# F4FlightController.net
KiCad netlist of a schematic drawn in Altium Designer
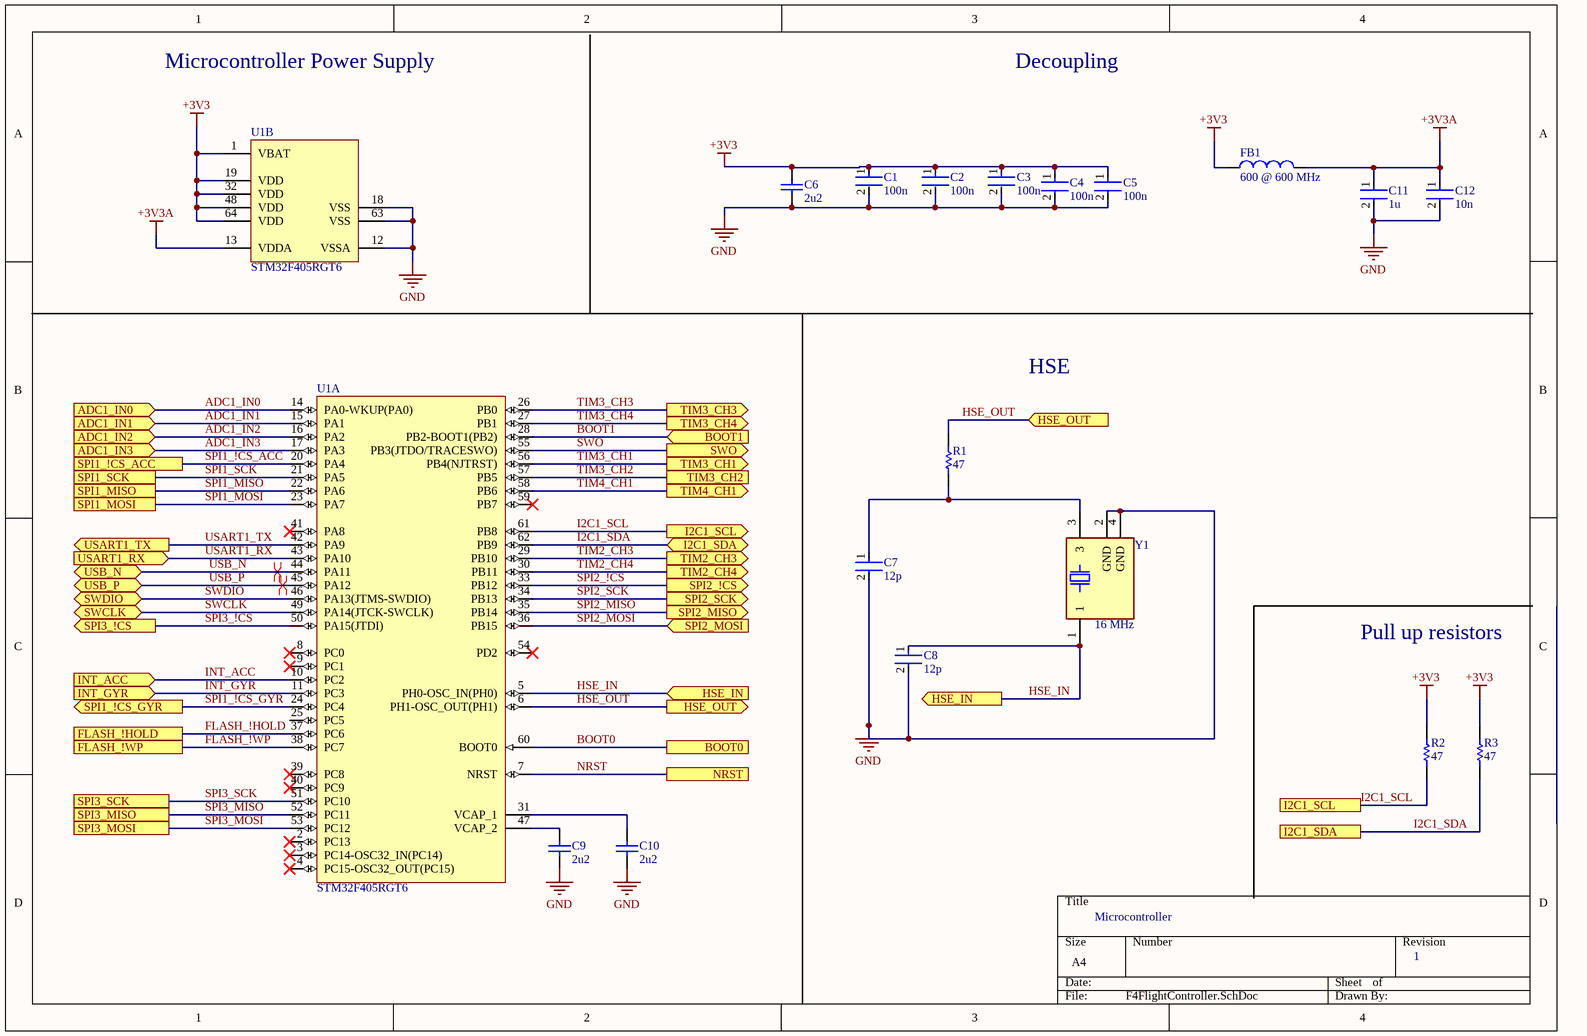
[diagram p0: F4FlightController.SchDoc]

(export (version "E")
  (design (tool "Eeschema 10.0.6"))
  (components
    (comp (ref "C1")
      (value "100n")
      (footprint "Capacitor 0402")
      (description "Chip Capacitor 0402")
      (fields (field (name "MANUFACTURER PART NUMBER") "CC0402KRX7R7BB103") (field (name "TOLERANCE") "0.1"))
      (libsource (lib "F4_Flight_Controller") (part "Capacitor 0402"))
    )
    (comp (ref "C2")
      (value "100n")
      (footprint "Capacitor 0402")
      (description "Chip Capacitor 0402")
      (fields (field (name "MANUFACTURER PART NUMBER") "CC0402KRX7R7BB103") (field (name "TOLERANCE") "0.1"))
      (libsource (lib "F4_Flight_Controller") (part "Capacitor 0402"))
    )
    (comp (ref "C3")
      (value "100n")
      (footprint "Capacitor 0402")
      (description "Chip Capacitor 0402")
      (fields (field (name "MANUFACTURER PART NUMBER") "CC0402KRX7R7BB103") (field (name "TOLERANCE") "0.1"))
      (libsource (lib "F4_Flight_Controller") (part "Capacitor 0402"))
    )
    (comp (ref "C4")
      (value "100n")
      (footprint "Capacitor 0402")
      (description "Chip Capacitor 0402")
      (fields (field (name "MANUFACTURER PART NUMBER") "CC0402KRX7R7BB103") (field (name "TOLERANCE") "0.1"))
      (libsource (lib "F4_Flight_Controller") (part "Capacitor 0402"))
    )
    (comp (ref "C5")
      (value "100n")
      (footprint "Capacitor 0402")
      (description "Chip Capacitor 0402")
      (fields (field (name "MANUFACTURER PART NUMBER") "CC0402KRX7R7BB103") (field (name "TOLERANCE") "0.1"))
      (libsource (lib "F4_Flight_Controller") (part "Capacitor 0402"))
    )
    (comp (ref "C6")
      (value "2u2")
      (footprint "CAPACITOR 0603")
      (description "Chip Capacitor, 22 pF, +/- 5%, 50 V, -55 to 125 degC, 0603 (1608 Metric), RoHS, Tape and Reel")
      (fields
        (field (name "MANUFACTURER") "Murata")
        (field (name "MANUFACTURER PART NUMBER") "GRM1885C1H220JA01D")
      )
      (libsource (lib "F4_Flight_Controller") (part "Chip Capacitor 0603"))
    )
    (comp (ref "C7")
      (value "12p")
      (footprint "Capacitor 0402")
      (description "Chip Capacitor 0402")
      (fields (field (name "MANUFACTURER PART NUMBER") "CC0402KRX7R7BB103") (field (name "TOLERANCE") "0.1"))
      (libsource (lib "F4_Flight_Controller") (part "Capacitor 0402"))
    )
    (comp (ref "C8")
      (value "12p")
      (footprint "Capacitor 0402")
      (description "Chip Capacitor 0402")
      (fields (field (name "MANUFACTURER PART NUMBER") "CC0402KRX7R7BB103") (field (name "TOLERANCE") "0.1"))
      (libsource (lib "F4_Flight_Controller") (part "Capacitor 0402"))
    )
    (comp (ref "C9")
      (value "2u2")
      (footprint "CAPACITOR 0603")
      (description "Chip Capacitor, 22 pF, +/- 5%, 50 V, -55 to 125 degC, 0603 (1608 Metric), RoHS, Tape and Reel")
      (fields
        (field (name "MANUFACTURER") "Murata")
        (field (name "MANUFACTURER PART NUMBER") "GRM1885C1H220JA01D")
      )
      (libsource (lib "F4_Flight_Controller") (part "Capacitor 0603"))
    )
    (comp (ref "C10")
      (value "2u2")
      (footprint "CAPACITOR 0603")
      (description "Chip Capacitor, 22 pF, +/- 5%, 50 V, -55 to 125 degC, 0603 (1608 Metric), RoHS, Tape and Reel")
      (fields
        (field (name "MANUFACTURER") "Murata")
        (field (name "MANUFACTURER PART NUMBER") "GRM1885C1H220JA01D")
      )
      (libsource (lib "F4_Flight_Controller") (part "Capacitor 0603"))
    )
    (comp (ref "C11")
      (value "1u")
      (footprint "Capacitor 0402")
      (description "Chip Capacitor 0402")
      (fields (field (name "MANUFACTURER PART NUMBER") "CC0402KRX7R7BB103") (field (name "TOLERANCE") "0.1"))
      (libsource (lib "F4_Flight_Controller") (part "Capacitor 0402"))
    )
    (comp (ref "C12")
      (value "10n")
      (footprint "Capacitor 0402")
      (description "Chip Capacitor 0402")
      (fields (field (name "MANUFACTURER PART NUMBER") "CC0402KRX7R7BB103") (field (name "TOLERANCE") "0.1"))
      (libsource (lib "F4_Flight_Controller") (part "Capacitor 0402"))
    )
    (comp (ref "FB1")
      (value "600 @ 600 MHz")
      (footprint "Inductor 0805")
      (description "Ferrite Bead Murata BLM21AG601SN1D")
      (fields
        (field (name "MANUFACTURER") "TDK")
        (field (name "MANUFACTURER PART NUMBER") "MLZ2012A1R0MT000")
      )
      (libsource (lib "F4_Flight_Controller") (part "Ferrite Bead"))
    )
    (comp (ref "R1")
      (value "47")
      (footprint "Resistor 0402")
      (description "Chip Resistor 0402")
      (fields (field (name "MANUFACTURER") "Vishay") (field (name "PART NUMBER") "CRCW0402120RFKED"))
      (libsource (lib "F4_Flight_Controller") (part "Resistor 0402"))
    )
    (comp (ref "R2")
      (value "47")
      (footprint "Resistor 0402")
      (description "Chip Resistor 0402")
      (fields (field (name "MANUFACTURER") "Vishay") (field (name "PART NUMBER") "CRCW0402120RFKED"))
      (libsource (lib "F4_Flight_Controller") (part "Resistor 0402"))
    )
    (comp (ref "R3")
      (value "47")
      (footprint "Resistor 0402")
      (description "Chip Resistor 0402")
      (fields (field (name "MANUFACTURER") "Vishay") (field (name "PART NUMBER") "CRCW0402120RFKED"))
      (libsource (lib "F4_Flight_Controller") (part "Resistor 0402"))
    )
    (comp (ref "U1")
      (value "STM32F405RGT6")
      (footprint "STM-LQFP64_M")
      (fields (field (name "MANUFACTURER") "STMicroelectronics"))
      (libsource (lib "F4_Flight_Controller") (part "STM32 ARM Cortex-M4"))
    )
    (comp (ref "Y1")
      (value "16 MHz")
      (footprint "XTAL_TSX-3225_16.0000MF18X-AC3")
      (description "16MHz Â±10ppm Crystal 9pF 60 Ohms 4-SMD, No Lead")
      (fields (field (name "MP") "TSX-3225 16.0000MF18X-AC3") (field (name "MF") "EPSON"))
      (libsource (lib "F4_Flight_Controller") (part "TSX-3225_16.0000MF18X-AC3"))
    )
  )
  (nets
    (net (code "1") (name "+3V3") (class "Default")
      (node (ref "C1") (pin "1") (pinfunction "1_1") (pintype "passive"))
      (node (ref "C2") (pin "1") (pinfunction "1_1") (pintype "passive"))
      (node (ref "C3") (pin "1") (pinfunction "1_1") (pintype "passive"))
      (node (ref "C4") (pin "1") (pinfunction "1_1") (pintype "passive"))
      (node (ref "C5") (pin "1") (pinfunction "1_1") (pintype "passive"))
      (node (ref "C6") (pin "2") (pinfunction "2_2") (pintype "passive"))
      (node (ref "FB1") (pin "1") (pinfunction "1_1") (pintype "passive"))
      (node (ref "R2") (pin "2") (pinfunction "2_2") (pintype "passive"))
      (node (ref "R3") (pin "2") (pinfunction "2_2") (pintype "passive"))
      (node (ref "U1") (pin "1") (pinfunction "VBAT_1") (pintype "power_in"))
      (node (ref "U1") (pin "19") (pinfunction "VDD_19") (pintype "power_in"))
      (node (ref "U1") (pin "32") (pinfunction "VDD_32") (pintype "power_in"))
      (node (ref "U1") (pin "48") (pinfunction "VDD_48") (pintype "power_in"))
      (node (ref "U1") (pin "64") (pinfunction "VDD_64") (pintype "power_in"))
    )
    (net (code "2") (name "+3V3A") (class "Default")
      (node (ref "C11") (pin "1") (pinfunction "1_1") (pintype "passive"))
      (node (ref "C12") (pin "1") (pinfunction "1_1") (pintype "passive"))
      (node (ref "FB1") (pin "2") (pinfunction "2_2") (pintype "passive"))
      (node (ref "U1") (pin "13") (pinfunction "VDDA_13") (pintype "power_in"))
    )
    (net (code "3") (name "/ADC1_IN0") (class "Default")
      (node (ref "U1") (pin "14") (pinfunction "PA0-WKUP(PA0)_14") (pintype "bidirectional"))
    )
    (net (code "4") (name "/ADC1_IN1") (class "Default")
      (node (ref "U1") (pin "15") (pinfunction "PA1_15") (pintype "bidirectional"))
    )
    (net (code "5") (name "/ADC1_IN2") (class "Default")
      (node (ref "U1") (pin "16") (pinfunction "PA2_16") (pintype "bidirectional"))
    )
    (net (code "6") (name "/ADC1_IN3") (class "Default")
      (node (ref "U1") (pin "17") (pinfunction "PA3_17") (pintype "bidirectional"))
    )
    (net (code "7") (name "/BOOT0") (class "Default")
      (node (ref "U1") (pin "60") (pinfunction "BOOT0_60") (pintype "input"))
    )
    (net (code "8") (name "/BOOT1") (class "Default")
      (node (ref "U1") (pin "28") (pinfunction "PB2-BOOT1(PB2)_28") (pintype "bidirectional"))
    )
    (net (code "9") (name "/FLASH_!HOLD") (class "Default")
      (node (ref "U1") (pin "37") (pinfunction "PC6_37") (pintype "bidirectional"))
    )
    (net (code "10") (name "/FLASH_!WP") (class "Default")
      (node (ref "U1") (pin "38") (pinfunction "PC7_38") (pintype "bidirectional"))
    )
    (net (code "11") (name "/HSE_IN") (class "Default")
      (node (ref "C8") (pin "1") (pinfunction "1_1") (pintype "passive"))
      (node (ref "U1") (pin "5") (pinfunction "PH0-OSC_IN(PH0)_5") (pintype "bidirectional"))
      (node (ref "Y1") (pin "1") (pinfunction "1_1") (pintype "passive"))
    )
    (net (code "12") (name "/HSE_OUT") (class "Default")
      (node (ref "R1") (pin "2") (pinfunction "2_2") (pintype "passive"))
      (node (ref "U1") (pin "6") (pinfunction "PH1-OSC_OUT(PH1)_6") (pintype "bidirectional"))
    )
    (net (code "13") (name "/I2C1_SCL") (class "Default")
      (node (ref "R2") (pin "1") (pinfunction "1_1") (pintype "passive"))
      (node (ref "U1") (pin "61") (pinfunction "PB8_61") (pintype "bidirectional"))
    )
    (net (code "14") (name "/I2C1_SDA") (class "Default")
      (node (ref "R3") (pin "1") (pinfunction "1_1") (pintype "passive"))
      (node (ref "U1") (pin "62") (pinfunction "PB9_62") (pintype "bidirectional"))
    )
    (net (code "15") (name "/INT_ACC") (class "Default")
      (node (ref "U1") (pin "10") (pinfunction "PC2_10") (pintype "bidirectional"))
    )
    (net (code "16") (name "/INT_GYR") (class "Default")
      (node (ref "U1") (pin "11") (pinfunction "PC3_11") (pintype "bidirectional"))
    )
    (net (code "17") (name "/NRST") (class "Default")
      (node (ref "U1") (pin "7") (pinfunction "NRST_7") (pintype "bidirectional"))
    )
    (net (code "18") (name "/SPI1_!CS_ACC") (class "Default")
      (node (ref "U1") (pin "20") (pinfunction "PA4_20") (pintype "bidirectional"))
    )
    (net (code "19") (name "/SPI1_!CS_GYR") (class "Default")
      (node (ref "U1") (pin "24") (pinfunction "PC4_24") (pintype "bidirectional"))
    )
    (net (code "20") (name "/SPI1_MISO") (class "Default")
      (node (ref "U1") (pin "22") (pinfunction "PA6_22") (pintype "bidirectional"))
    )
    (net (code "21") (name "/SPI1_MOSI") (class "Default")
      (node (ref "U1") (pin "23") (pinfunction "PA7_23") (pintype "bidirectional"))
    )
    (net (code "22") (name "/SPI1_SCK") (class "Default")
      (node (ref "U1") (pin "21") (pinfunction "PA5_21") (pintype "bidirectional"))
    )
    (net (code "23") (name "/SPI2_!CS") (class "Default")
      (node (ref "U1") (pin "33") (pinfunction "PB12_33") (pintype "bidirectional"))
    )
    (net (code "24") (name "/SPI2_MISO") (class "Default")
      (node (ref "U1") (pin "35") (pinfunction "PB14_35") (pintype "bidirectional"))
    )
    (net (code "25") (name "/SPI2_MOSI") (class "Default")
      (node (ref "U1") (pin "36") (pinfunction "PB15_36") (pintype "bidirectional"))
    )
    (net (code "26") (name "/SPI2_SCK") (class "Default")
      (node (ref "U1") (pin "34") (pinfunction "PB13_34") (pintype "bidirectional"))
    )
    (net (code "27") (name "/SPI3_!CS") (class "Default")
      (node (ref "U1") (pin "50") (pinfunction "PA15(JTDI)_50") (pintype "bidirectional"))
    )
    (net (code "28") (name "/SPI3_MISO") (class "Default")
      (node (ref "U1") (pin "52") (pinfunction "PC11_52") (pintype "bidirectional"))
    )
    (net (code "29") (name "/SPI3_MOSI") (class "Default")
      (node (ref "U1") (pin "53") (pinfunction "PC12_53") (pintype "bidirectional"))
    )
    (net (code "30") (name "/SPI3_SCK") (class "Default")
      (node (ref "U1") (pin "51") (pinfunction "PC10_51") (pintype "bidirectional"))
    )
    (net (code "31") (name "/SWCLK") (class "Default")
      (node (ref "U1") (pin "49") (pinfunction "PA14(JTCK-SWCLK)_49") (pintype "bidirectional"))
    )
    (net (code "32") (name "/SWDIO") (class "Default")
      (node (ref "U1") (pin "46") (pinfunction "PA13(JTMS-SWDIO)_46") (pintype "bidirectional"))
    )
    (net (code "33") (name "/SWO") (class "Default")
      (node (ref "U1") (pin "55") (pinfunction "PB3(JTDO/TRACESWO)_55") (pintype "bidirectional"))
    )
    (net (code "34") (name "/TIM2_CH3") (class "Default")
      (node (ref "U1") (pin "29") (pinfunction "PB10_29") (pintype "bidirectional"))
    )
    (net (code "35") (name "/TIM2_CH4") (class "Default")
      (node (ref "U1") (pin "30") (pinfunction "PB11_30") (pintype "bidirectional"))
    )
    (net (code "36") (name "/TIM3_CH1") (class "Default")
      (node (ref "U1") (pin "56") (pinfunction "PB4(NJTRST)_56") (pintype "bidirectional"))
    )
    (net (code "37") (name "/TIM3_CH2") (class "Default")
      (node (ref "U1") (pin "57") (pinfunction "PB5_57") (pintype "bidirectional"))
    )
    (net (code "38") (name "/TIM3_CH3") (class "Default")
      (node (ref "U1") (pin "26") (pinfunction "PB0_26") (pintype "bidirectional"))
    )
    (net (code "39") (name "/TIM3_CH4") (class "Default")
      (node (ref "U1") (pin "27") (pinfunction "PB1_27") (pintype "bidirectional"))
    )
    (net (code "40") (name "/TIM4_CH1") (class "Default")
      (node (ref "U1") (pin "58") (pinfunction "PB6_58") (pintype "bidirectional"))
    )
    (net (code "41") (name "/USART1_RX") (class "Default")
      (node (ref "U1") (pin "43") (pinfunction "PA10_43") (pintype "bidirectional"))
    )
    (net (code "42") (name "/USART1_TX") (class "Default")
      (node (ref "U1") (pin "42") (pinfunction "PA9_42") (pintype "bidirectional"))
    )
    (net (code "43") (name "/USB_N") (class "Default")
      (node (ref "U1") (pin "44") (pinfunction "PA11_44") (pintype "bidirectional"))
    )
    (net (code "44") (name "/USB_P") (class "Default")
      (node (ref "U1") (pin "45") (pinfunction "PA12_45") (pintype "bidirectional"))
    )
    (net (code "45") (name "GND") (class "Default")
      (node (ref "C1") (pin "2") (pinfunction "2_2") (pintype "passive"))
      (node (ref "C10") (pin "1") (pinfunction "1_1") (pintype "passive"))
      (node (ref "C11") (pin "2") (pinfunction "2_2") (pintype "passive"))
      (node (ref "C12") (pin "2") (pinfunction "2_2") (pintype "passive"))
      (node (ref "C2") (pin "2") (pinfunction "2_2") (pintype "passive"))
      (node (ref "C3") (pin "2") (pinfunction "2_2") (pintype "passive"))
      (node (ref "C4") (pin "2") (pinfunction "2_2") (pintype "passive"))
      (node (ref "C5") (pin "2") (pinfunction "2_2") (pintype "passive"))
      (node (ref "C6") (pin "1") (pinfunction "1_1") (pintype "passive"))
      (node (ref "C7") (pin "2") (pinfunction "2_2") (pintype "passive"))
      (node (ref "C8") (pin "2") (pinfunction "2_2") (pintype "passive"))
      (node (ref "C9") (pin "1") (pinfunction "1_1") (pintype "passive"))
      (node (ref "U1") (pin "12") (pinfunction "VSSA_12") (pintype "power_in"))
      (node (ref "U1") (pin "18") (pinfunction "VSS_18") (pintype "power_in"))
      (node (ref "U1") (pin "63") (pinfunction "VSS_63") (pintype "power_in"))
      (node (ref "Y1") (pin "2") (pinfunction "GND_2") (pintype "power_in"))
      (node (ref "Y1") (pin "4") (pinfunction "GND_4") (pintype "power_in"))
    )
    (net (code "46") (name "Net-(C7-Pad1)") (class "Default")
      (node (ref "C7") (pin "1") (pinfunction "1_1") (pintype "passive"))
      (node (ref "R1") (pin "1") (pinfunction "1_1") (pintype "passive"))
      (node (ref "Y1") (pin "3") (pinfunction "3_3") (pintype "passive"))
    )
    (net (code "47") (name "Net-(U1A-VCAP_1)") (class "Default")
      (node (ref "C10") (pin "2") (pinfunction "2_2") (pintype "passive"))
      (node (ref "U1") (pin "31") (pinfunction "VCAP_1_31") (pintype "power_in"))
    )
    (net (code "48") (name "Net-(U1A-VCAP_2)") (class "Default")
      (node (ref "C9") (pin "2") (pinfunction "2_2") (pintype "passive"))
      (node (ref "U1") (pin "47") (pinfunction "VCAP_2_47") (pintype "power_in"))
    )
    (net (code "49") (name "unconnected-(U1A-PA8-Pad41)") (class "Default")
      (node (ref "U1") (pin "41") (pinfunction "PA8_41") (pintype "bidirectional+no_connect"))
    )
    (net (code "50") (name "unconnected-(U1A-PB7-Pad59)") (class "Default")
      (node (ref "U1") (pin "59") (pinfunction "PB7_59") (pintype "bidirectional+no_connect"))
    )
    (net (code "51") (name "unconnected-(U1A-PC0-Pad8)") (class "Default")
      (node (ref "U1") (pin "8") (pinfunction "PC0_8") (pintype "bidirectional+no_connect"))
    )
    (net (code "52") (name "unconnected-(U1A-PC1-Pad9)") (class "Default")
      (node (ref "U1") (pin "9") (pinfunction "PC1_9") (pintype "bidirectional+no_connect"))
    )
    (net (code "53") (name "unconnected-(U1A-PC5-Pad25)") (class "Default")
      (node (ref "U1") (pin "25") (pinfunction "PC5_25") (pintype "bidirectional"))
    )
    (net (code "54") (name "unconnected-(U1A-PC8-Pad39)") (class "Default")
      (node (ref "U1") (pin "39") (pinfunction "PC8_39") (pintype "bidirectional+no_connect"))
    )
    (net (code "55") (name "unconnected-(U1A-PC9-Pad40)") (class "Default")
      (node (ref "U1") (pin "40") (pinfunction "PC9_40") (pintype "bidirectional+no_connect"))
    )
    (net (code "56") (name "unconnected-(U1A-PC13-Pad2)") (class "Default")
      (node (ref "U1") (pin "2") (pinfunction "PC13_2") (pintype "bidirectional+no_connect"))
    )
    (net (code "57") (name "unconnected-(U1A-PC14-OSC32_IN(PC14)-Pad3)") (class "Default")
      (node (ref "U1") (pin "3") (pinfunction "PC14-OSC32_IN(PC14)_3") (pintype "bidirectional+no_connect"))
    )
    (net (code "58") (name "unconnected-(U1A-PC15-OSC32_OUT(PC15)-Pad4)") (class "Default")
      (node (ref "U1") (pin "4") (pinfunction "PC15-OSC32_OUT(PC15)_4") (pintype "bidirectional+no_connect"))
    )
    (net (code "59") (name "unconnected-(U1A-PD2-Pad54)") (class "Default")
      (node (ref "U1") (pin "54") (pinfunction "PD2_54") (pintype "bidirectional+no_connect"))
    )
  )
)
